# TubeBoard.net
KiCad netlist of a schematic drawn in EAGLE
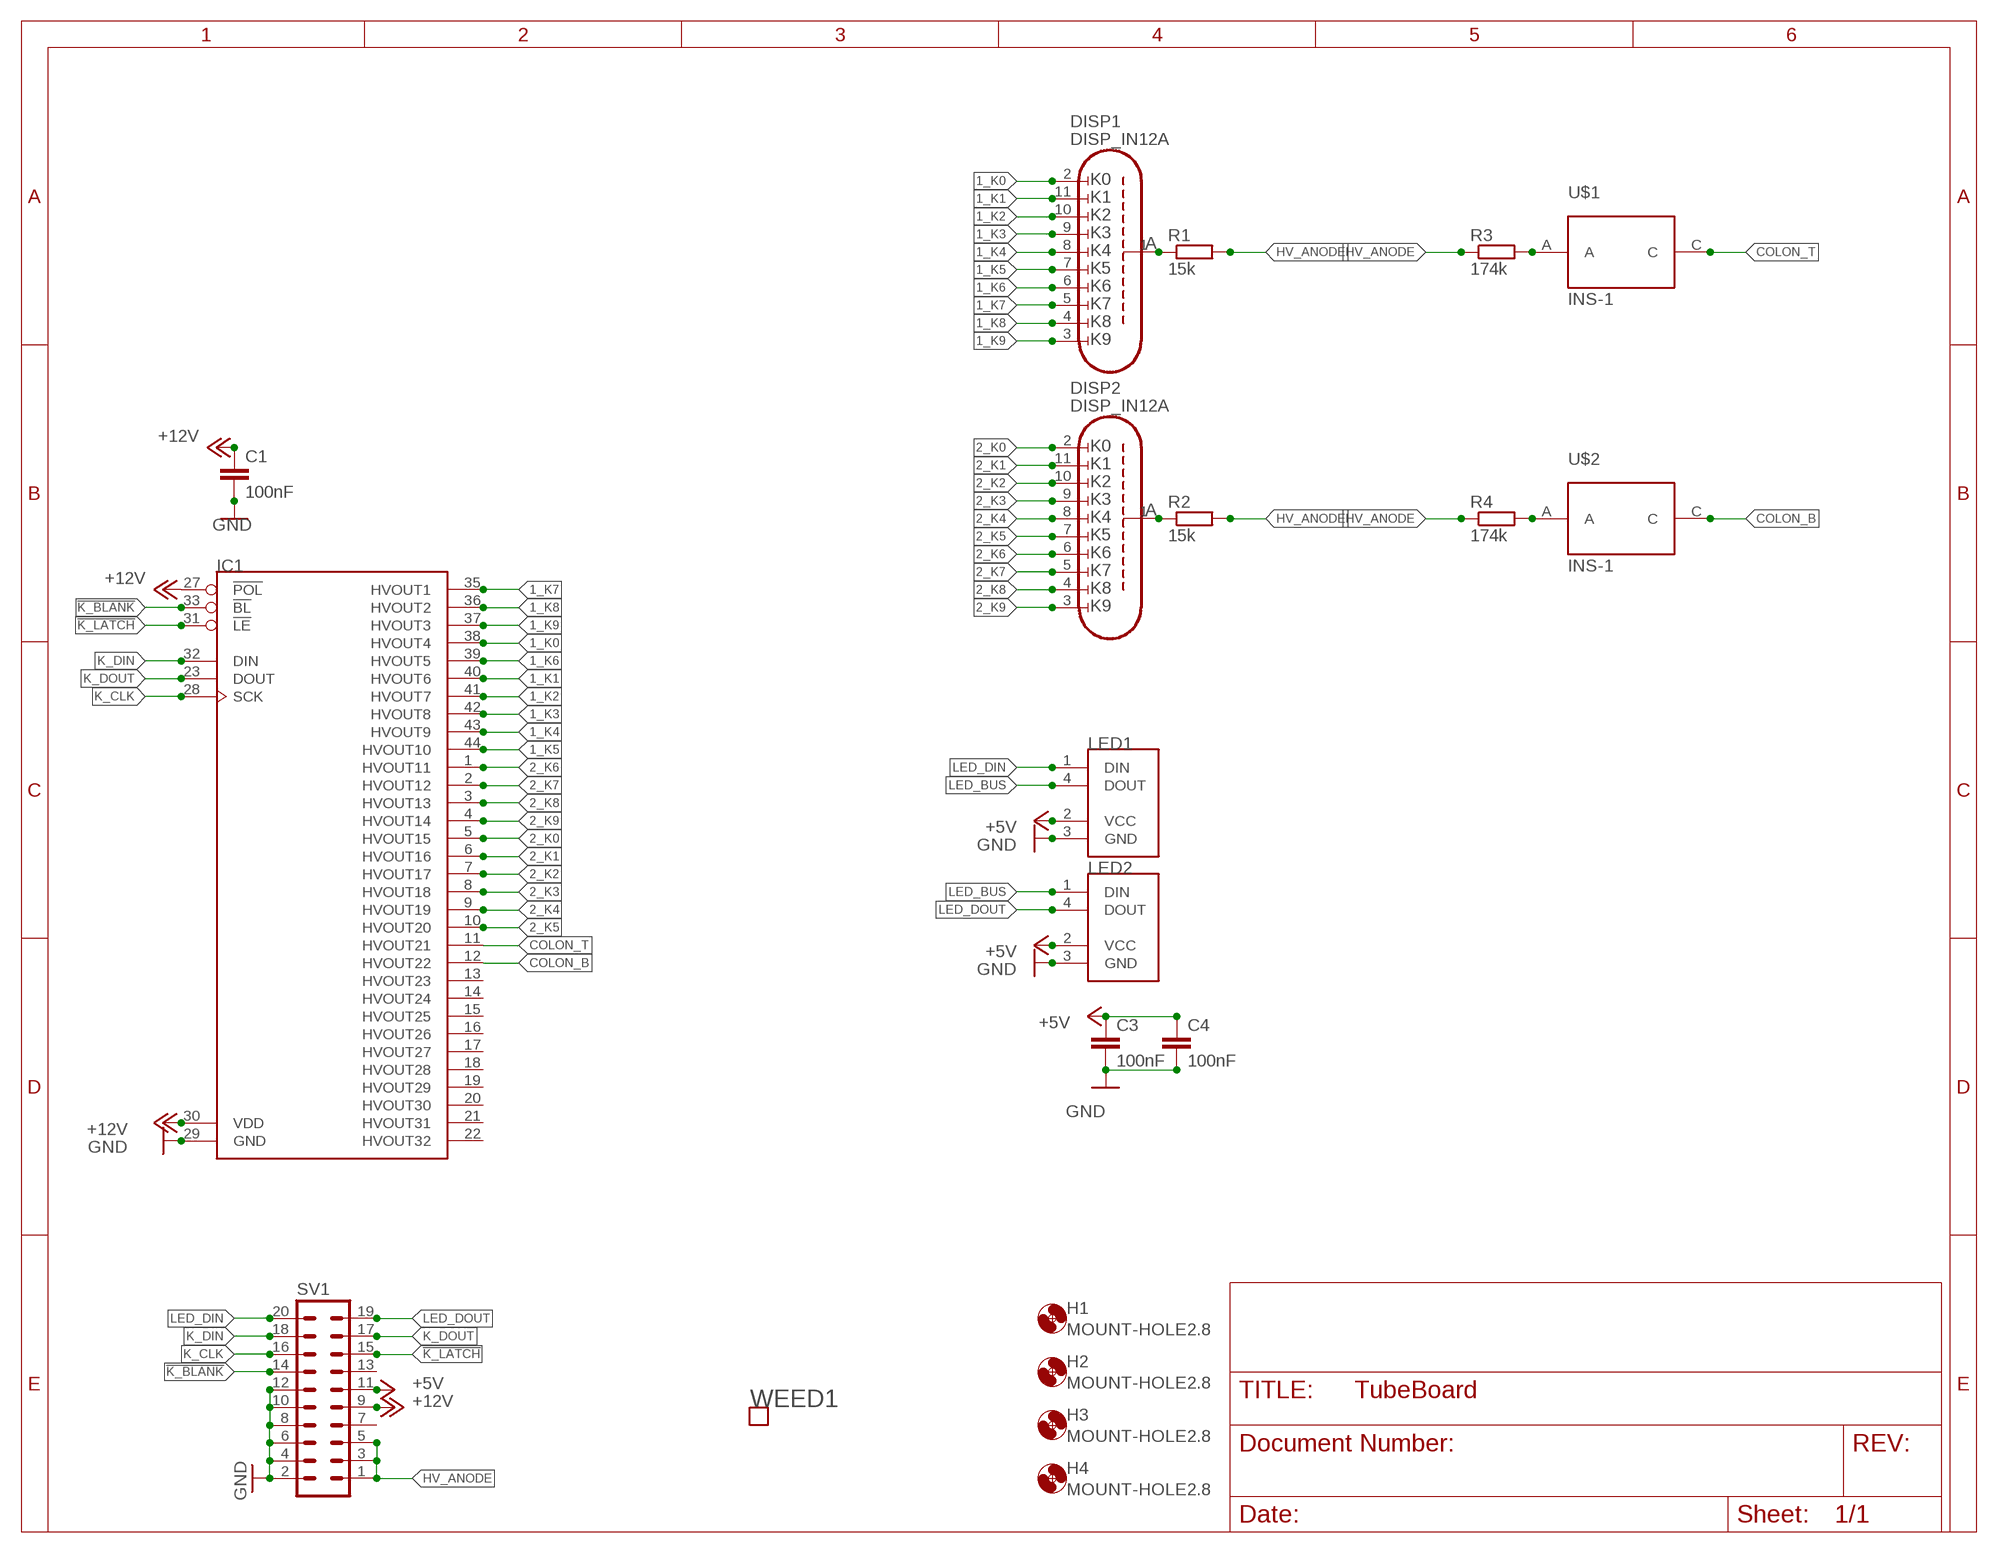
[diagram p0: schematic, sheet 1]

(export (version "E")
  (design (tool "Eeschema 10.0.6"))
  (components
    (comp (ref "C1")
      (value "100nF")
      (footprint "eagle-import:C1206")
      (libsource (lib "eagle-import") (part "C-EUC1206"))
    )
    (comp (ref "C3")
      (value "100nF")
      (footprint "eagle-import:C1206")
      (libsource (lib "eagle-import") (part "C-EUC1206"))
    )
    (comp (ref "C4")
      (value "100nF")
      (footprint "eagle-import:C1206")
      (libsource (lib "eagle-import") (part "C-EUC1206"))
    )
    (comp (ref "DISP1")
      (value "DISP_IN12A")
      (footprint "eagle-import:DISP_IN-12_SOCKET")
      (libsource (lib "eagle-import") (part "DISP_IN12A"))
    )
    (comp (ref "DISP2")
      (value "DISP_IN12A")
      (footprint "eagle-import:DISP_IN-12_SOCKET")
      (libsource (lib "eagle-import") (part "DISP_IN12A"))
    )
    (comp (ref "H1")
      (value "MOUNT-HOLE2.8")
      (footprint "eagle-import:2,8")
      (libsource (lib "eagle-import") (part "MOUNT-HOLE2.8"))
    )
    (comp (ref "H2")
      (value "MOUNT-HOLE2.8")
      (footprint "eagle-import:2,8")
      (libsource (lib "eagle-import") (part "MOUNT-HOLE2.8"))
    )
    (comp (ref "H3")
      (value "MOUNT-HOLE2.8")
      (footprint "eagle-import:2,8")
      (libsource (lib "eagle-import") (part "MOUNT-HOLE2.8"))
    )
    (comp (ref "H4")
      (value "MOUNT-HOLE2.8")
      (footprint "eagle-import:2,8")
      (libsource (lib "eagle-import") (part "MOUNT-HOLE2.8"))
    )
    (comp (ref "IC1")
      (value "HV5530PQFP-44")
      (footprint "eagle-import:PQFP44")
      (libsource (lib "eagle-import") (part "HV5530PQFP-44"))
    )
    (comp (ref "LED1")
      (value "NEOPIXEL-5MMLED-4PIN")
      (footprint "eagle-import:LED5MMRGB")
      (libsource (lib "eagle-import") (part "NEOPIXEL-5MMLED-4PIN"))
    )
    (comp (ref "LED2")
      (value "NEOPIXEL-5MMLED-4PIN")
      (footprint "eagle-import:LED5MMRGB")
      (libsource (lib "eagle-import") (part "NEOPIXEL-5MMLED-4PIN"))
    )
    (comp (ref "R1")
      (value "15k")
      (footprint "eagle-import:0411_12")
      (libsource (lib "eagle-import") (part "R-EU_0411/12"))
    )
    (comp (ref "R2")
      (value "15k")
      (footprint "eagle-import:0411_12")
      (libsource (lib "eagle-import") (part "R-EU_0411/12"))
    )
    (comp (ref "R3")
      (value "174k")
      (footprint "eagle-import:M1206")
      (libsource (lib "eagle-import") (part "R-EU_M1206"))
    )
    (comp (ref "R4")
      (value "174k")
      (footprint "eagle-import:M1206")
      (libsource (lib "eagle-import") (part "R-EU_M1206"))
    )
    (comp (ref "SV1")
      (value "MA10-2")
      (footprint "eagle-import:MA10-2")
      (libsource (lib "eagle-import") (part "MA10-2"))
    )
    (comp (ref "U$1")
      (value "INS-1")
      (footprint "eagle-import:INS-1")
      (libsource (lib "eagle-import") (part "INS-1"))
    )
    (comp (ref "U$2")
      (value "INS-1")
      (footprint "eagle-import:INS-1")
      (libsource (lib "eagle-import") (part "INS-1"))
    )
    (comp (ref "WEED1")
      (value "WEED")
      (footprint "eagle-import:DOINK")
      (libsource (lib "eagle-import") (part "WEED"))
    )
  )
  (nets
    (net (code "1") (name "+5V") (class "Default")
      (node (ref "C3") (pin "1") (pinfunction "1_1") (pintype "passive"))
      (node (ref "C4") (pin "1") (pinfunction "1_1") (pintype "passive"))
      (node (ref "LED1") (pin "2") (pinfunction "VCC_2") (pintype "power_in"))
      (node (ref "LED2") (pin "2") (pinfunction "VCC_2") (pintype "power_in"))
      (node (ref "SV1") (pin "11") (pinfunction "11_11") (pintype "passive"))
    )
    (net (code "2") (name "+12V") (class "Default")
      (node (ref "C1") (pin "1") (pinfunction "1_1") (pintype "passive"))
      (node (ref "IC1") (pin "27") (pinfunction "~{POL}_27") (pintype "bidirectional"))
      (node (ref "IC1") (pin "30") (pinfunction "VDD_30") (pintype "power_in"))
      (node (ref "SV1") (pin "9") (pinfunction "9_9") (pintype "passive"))
    )
    (net (code "3") (name "/~{K_BLANK}") (class "Default")
      (node (ref "IC1") (pin "33") (pinfunction "~{BL}_33") (pintype "bidirectional"))
      (node (ref "SV1") (pin "14") (pinfunction "14_14") (pintype "passive"))
    )
    (net (code "4") (name "/~{K_LATCH}") (class "Default")
      (node (ref "IC1") (pin "31") (pinfunction "~{LE}_31") (pintype "bidirectional"))
      (node (ref "SV1") (pin "15") (pinfunction "15_15") (pintype "passive"))
    )
    (net (code "5") (name "1_K0") (class "Default")
      (node (ref "DISP1") (pin "2") (pinfunction "K0_2") (pintype "input"))
      (node (ref "IC1") (pin "38") (pinfunction "HVOUT4_38") (pintype "bidirectional"))
    )
    (net (code "6") (name "1_K1") (class "Default")
      (node (ref "DISP1") (pin "11") (pinfunction "K1_11") (pintype "input"))
      (node (ref "IC1") (pin "40") (pinfunction "HVOUT6_40") (pintype "bidirectional"))
    )
    (net (code "7") (name "1_K2") (class "Default")
      (node (ref "DISP1") (pin "10") (pinfunction "K2_10") (pintype "input"))
      (node (ref "IC1") (pin "41") (pinfunction "HVOUT7_41") (pintype "bidirectional"))
    )
    (net (code "8") (name "1_K3") (class "Default")
      (node (ref "DISP1") (pin "9") (pinfunction "K3_9") (pintype "input"))
      (node (ref "IC1") (pin "42") (pinfunction "HVOUT8_42") (pintype "bidirectional"))
    )
    (net (code "9") (name "1_K4") (class "Default")
      (node (ref "DISP1") (pin "8") (pinfunction "K4_8") (pintype "input"))
      (node (ref "IC1") (pin "43") (pinfunction "HVOUT9_43") (pintype "bidirectional"))
    )
    (net (code "10") (name "1_K5") (class "Default")
      (node (ref "DISP1") (pin "7") (pinfunction "K5_7") (pintype "input"))
      (node (ref "IC1") (pin "44") (pinfunction "HVOUT10_44") (pintype "bidirectional"))
    )
    (net (code "11") (name "1_K6") (class "Default")
      (node (ref "DISP1") (pin "6") (pinfunction "K6_6") (pintype "input"))
      (node (ref "IC1") (pin "39") (pinfunction "HVOUT5_39") (pintype "bidirectional"))
    )
    (net (code "12") (name "1_K7") (class "Default")
      (node (ref "DISP1") (pin "5") (pinfunction "K7_5") (pintype "input"))
      (node (ref "IC1") (pin "35") (pinfunction "HVOUT1_35") (pintype "bidirectional"))
    )
    (net (code "13") (name "1_K8") (class "Default")
      (node (ref "DISP1") (pin "4") (pinfunction "K8_4") (pintype "input"))
      (node (ref "IC1") (pin "36") (pinfunction "HVOUT2_36") (pintype "bidirectional"))
    )
    (net (code "14") (name "1_K9") (class "Default")
      (node (ref "DISP1") (pin "3") (pinfunction "K9_3") (pintype "input"))
      (node (ref "IC1") (pin "37") (pinfunction "HVOUT3_37") (pintype "bidirectional"))
    )
    (net (code "15") (name "2_K0") (class "Default")
      (node (ref "DISP2") (pin "2") (pinfunction "K0_2") (pintype "input"))
      (node (ref "IC1") (pin "5") (pinfunction "HVOUT15_5") (pintype "bidirectional"))
    )
    (net (code "16") (name "2_K1") (class "Default")
      (node (ref "DISP2") (pin "11") (pinfunction "K1_11") (pintype "input"))
      (node (ref "IC1") (pin "6") (pinfunction "HVOUT16_6") (pintype "bidirectional"))
    )
    (net (code "17") (name "2_K2") (class "Default")
      (node (ref "DISP2") (pin "10") (pinfunction "K2_10") (pintype "input"))
      (node (ref "IC1") (pin "7") (pinfunction "HVOUT17_7") (pintype "bidirectional"))
    )
    (net (code "18") (name "2_K3") (class "Default")
      (node (ref "DISP2") (pin "9") (pinfunction "K3_9") (pintype "input"))
      (node (ref "IC1") (pin "8") (pinfunction "HVOUT18_8") (pintype "bidirectional"))
    )
    (net (code "19") (name "2_K4") (class "Default")
      (node (ref "DISP2") (pin "8") (pinfunction "K4_8") (pintype "input"))
      (node (ref "IC1") (pin "9") (pinfunction "HVOUT19_9") (pintype "bidirectional"))
    )
    (net (code "20") (name "2_K5") (class "Default")
      (node (ref "DISP2") (pin "7") (pinfunction "K5_7") (pintype "input"))
      (node (ref "IC1") (pin "10") (pinfunction "HVOUT20_10") (pintype "bidirectional"))
    )
    (net (code "21") (name "2_K6") (class "Default")
      (node (ref "DISP2") (pin "6") (pinfunction "K6_6") (pintype "input"))
      (node (ref "IC1") (pin "1") (pinfunction "HVOUT11_1") (pintype "bidirectional"))
    )
    (net (code "22") (name "2_K7") (class "Default")
      (node (ref "DISP2") (pin "5") (pinfunction "K7_5") (pintype "input"))
      (node (ref "IC1") (pin "2") (pinfunction "HVOUT12_2") (pintype "bidirectional"))
    )
    (net (code "23") (name "2_K8") (class "Default")
      (node (ref "DISP2") (pin "4") (pinfunction "K8_4") (pintype "input"))
      (node (ref "IC1") (pin "3") (pinfunction "HVOUT13_3") (pintype "bidirectional"))
    )
    (net (code "24") (name "2_K9") (class "Default")
      (node (ref "DISP2") (pin "3") (pinfunction "K9_3") (pintype "input"))
      (node (ref "IC1") (pin "4") (pinfunction "HVOUT14_4") (pintype "bidirectional"))
    )
    (net (code "25") (name "COLON_B") (class "Default")
      (node (ref "IC1") (pin "12") (pinfunction "HVOUT22_12") (pintype "bidirectional"))
      (node (ref "U$2") (pin "C") (pinfunction "C_C") (pintype "bidirectional"))
    )
    (net (code "26") (name "COLON_T") (class "Default")
      (node (ref "IC1") (pin "11") (pinfunction "HVOUT21_11") (pintype "bidirectional"))
      (node (ref "U$1") (pin "C") (pinfunction "C_C") (pintype "bidirectional"))
    )
    (net (code "27") (name "GND") (class "Default")
      (node (ref "C1") (pin "2") (pinfunction "2_2") (pintype "passive"))
      (node (ref "C3") (pin "2") (pinfunction "2_2") (pintype "passive"))
      (node (ref "C4") (pin "2") (pinfunction "2_2") (pintype "passive"))
      (node (ref "IC1") (pin "29") (pinfunction "GND_29") (pintype "power_in"))
      (node (ref "LED1") (pin "3") (pinfunction "GND_3") (pintype "power_in"))
      (node (ref "LED2") (pin "3") (pinfunction "GND_3") (pintype "power_in"))
      (node (ref "SV1") (pin "10") (pinfunction "10_10") (pintype "passive"))
      (node (ref "SV1") (pin "12") (pinfunction "12_12") (pintype "passive"))
      (node (ref "SV1") (pin "2") (pinfunction "2_2") (pintype "passive"))
      (node (ref "SV1") (pin "4") (pinfunction "4_4") (pintype "passive"))
      (node (ref "SV1") (pin "6") (pinfunction "6_6") (pintype "passive"))
      (node (ref "SV1") (pin "8") (pinfunction "8_8") (pintype "passive"))
    )
    (net (code "28") (name "HV_ANODE") (class "Default")
      (node (ref "R1") (pin "2") (pinfunction "2_2") (pintype "passive"))
      (node (ref "R2") (pin "2") (pinfunction "2_2") (pintype "passive"))
      (node (ref "R3") (pin "1") (pinfunction "1_1") (pintype "passive"))
      (node (ref "R4") (pin "1") (pinfunction "1_1") (pintype "passive"))
      (node (ref "SV1") (pin "1") (pinfunction "1_1") (pintype "passive"))
      (node (ref "SV1") (pin "3") (pinfunction "3_3") (pintype "passive"))
      (node (ref "SV1") (pin "5") (pinfunction "5_5") (pintype "passive"))
    )
    (net (code "29") (name "K_CLK") (class "Default")
      (node (ref "IC1") (pin "28") (pinfunction "SCK_28") (pintype "bidirectional"))
      (node (ref "SV1") (pin "16") (pinfunction "16_16") (pintype "passive"))
    )
    (net (code "30") (name "K_DIN") (class "Default")
      (node (ref "IC1") (pin "32") (pinfunction "DIN_32") (pintype "bidirectional"))
      (node (ref "SV1") (pin "18") (pinfunction "18_18") (pintype "passive"))
    )
    (net (code "31") (name "K_DOUT") (class "Default")
      (node (ref "IC1") (pin "23") (pinfunction "DOUT_23") (pintype "bidirectional"))
      (node (ref "SV1") (pin "17") (pinfunction "17_17") (pintype "passive"))
    )
    (net (code "32") (name "LED_BUS") (class "Default")
      (node (ref "LED1") (pin "4") (pinfunction "DOUT_4") (pintype "bidirectional"))
      (node (ref "LED2") (pin "1") (pinfunction "DIN_1") (pintype "bidirectional"))
    )
    (net (code "33") (name "LED_DIN") (class "Default")
      (node (ref "LED1") (pin "1") (pinfunction "DIN_1") (pintype "bidirectional"))
      (node (ref "SV1") (pin "20") (pinfunction "20_20") (pintype "passive"))
    )
    (net (code "34") (name "LED_DOUT") (class "Default")
      (node (ref "LED2") (pin "4") (pinfunction "DOUT_4") (pintype "bidirectional"))
      (node (ref "SV1") (pin "19") (pinfunction "19_19") (pintype "passive"))
    )
    (net (code "35") (name "Net-(DISP1-ANODE)") (class "Default")
      (node (ref "DISP1") (pin "1") (pinfunction "ANODE_1") (pintype "input"))
      (node (ref "R1") (pin "1") (pinfunction "1_1") (pintype "passive"))
    )
    (net (code "36") (name "Net-(DISP2-ANODE)") (class "Default")
      (node (ref "DISP2") (pin "1") (pinfunction "ANODE_1") (pintype "input"))
      (node (ref "R2") (pin "1") (pinfunction "1_1") (pintype "passive"))
    )
    (net (code "37") (name "Net-(R3-Pad2)") (class "Default")
      (node (ref "R3") (pin "2") (pinfunction "2_2") (pintype "passive"))
      (node (ref "U$1") (pin "A") (pinfunction "A_A") (pintype "bidirectional"))
    )
    (net (code "38") (name "Net-(R4-Pad2)") (class "Default")
      (node (ref "R4") (pin "2") (pinfunction "2_2") (pintype "passive"))
      (node (ref "U$2") (pin "A") (pinfunction "A_A") (pintype "bidirectional"))
    )
    (net (code "39") (name "unconnected-(IC1-HVOUT23-Pad13)") (class "Default")
      (node (ref "IC1") (pin "13") (pinfunction "HVOUT23_13") (pintype "bidirectional"))
    )
    (net (code "40") (name "unconnected-(IC1-HVOUT24-Pad14)") (class "Default")
      (node (ref "IC1") (pin "14") (pinfunction "HVOUT24_14") (pintype "bidirectional"))
    )
    (net (code "41") (name "unconnected-(IC1-HVOUT25-Pad15)") (class "Default")
      (node (ref "IC1") (pin "15") (pinfunction "HVOUT25_15") (pintype "bidirectional"))
    )
    (net (code "42") (name "unconnected-(IC1-HVOUT26-Pad16)") (class "Default")
      (node (ref "IC1") (pin "16") (pinfunction "HVOUT26_16") (pintype "bidirectional"))
    )
    (net (code "43") (name "unconnected-(IC1-HVOUT27-Pad17)") (class "Default")
      (node (ref "IC1") (pin "17") (pinfunction "HVOUT27_17") (pintype "bidirectional"))
    )
    (net (code "44") (name "unconnected-(IC1-HVOUT28-Pad18)") (class "Default")
      (node (ref "IC1") (pin "18") (pinfunction "HVOUT28_18") (pintype "bidirectional"))
    )
    (net (code "45") (name "unconnected-(IC1-HVOUT29-Pad19)") (class "Default")
      (node (ref "IC1") (pin "19") (pinfunction "HVOUT29_19") (pintype "bidirectional"))
    )
    (net (code "46") (name "unconnected-(IC1-HVOUT30-Pad20)") (class "Default")
      (node (ref "IC1") (pin "20") (pinfunction "HVOUT30_20") (pintype "bidirectional"))
    )
    (net (code "47") (name "unconnected-(IC1-HVOUT31-Pad21)") (class "Default")
      (node (ref "IC1") (pin "21") (pinfunction "HVOUT31_21") (pintype "bidirectional"))
    )
    (net (code "48") (name "unconnected-(IC1-HVOUT32-Pad22)") (class "Default")
      (node (ref "IC1") (pin "22") (pinfunction "HVOUT32_22") (pintype "bidirectional"))
    )
    (net (code "49") (name "unconnected-(SV1-Pad7)") (class "Default")
      (node (ref "SV1") (pin "7") (pinfunction "7_7") (pintype "passive"))
    )
    (net (code "50") (name "unconnected-(SV1-Pad13)") (class "Default")
      (node (ref "SV1") (pin "13") (pinfunction "13_13") (pintype "passive"))
    )
  )
)
